# Assignment4B-IR-Sensor_Schematic_sch.net
KiCad netlist of a schematic drawn in EAGLE
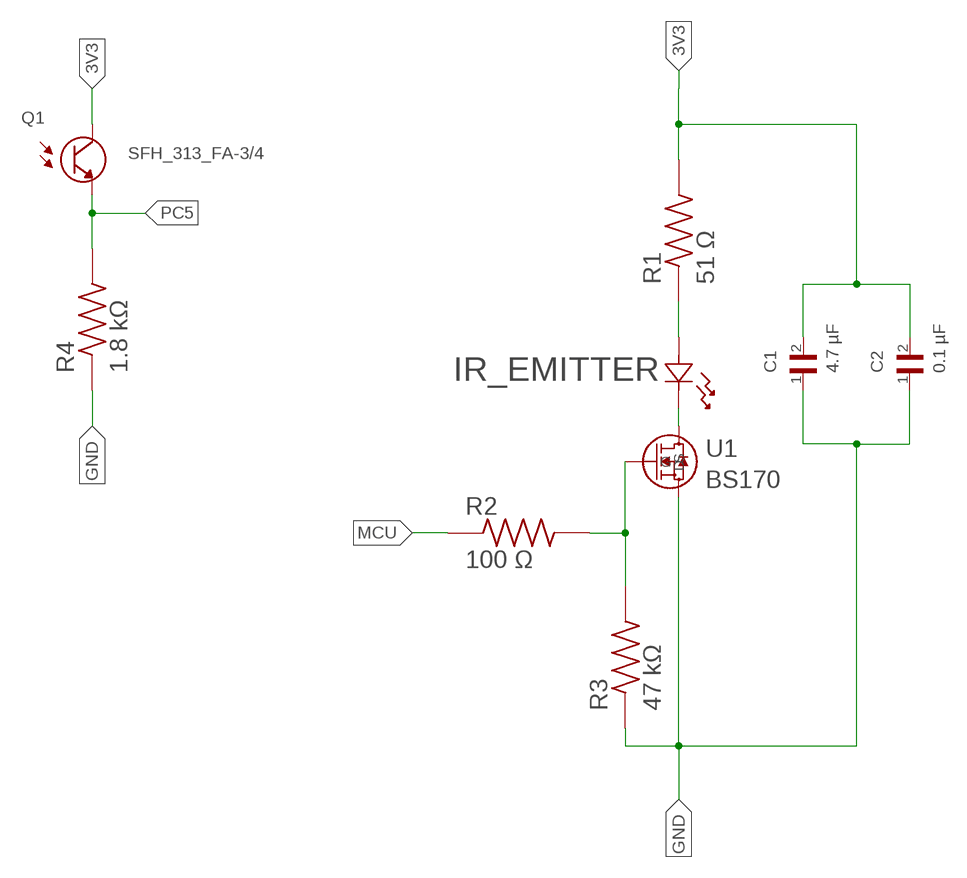
[diagram p0: schematic, sheet 1]

(export (version "E")
  (design (tool "Eeschema 10.0.6"))
  (components
    (comp (ref "C1")
      (value "4.7 µF")
      (footprint "eagle-import:CAPC2012X140N")
      (fields
        (field (name "DIGIKEY_PART_NUMBER") "490-14466-2-ND")
        (field (name "MF") "Murata Electronics")
        (field (name "MP") "GRM21BR71C475KE51L")
      )
      (libsource (lib "eagle-import") (part "GRM21BR71C475KE51L"))
    )
    (comp (ref "C2")
      (value "0.1 µF")
      (footprint "eagle-import:CAPC2012X140N")
      (fields (field (name "MF") "Murata") (field (name "MP") "GCM21BR72A104KA37K"))
      (libsource (lib "eagle-import") (part "GCM21BR72A104KA37K"))
    )
    (comp (ref "LED1")
      (value "IR_EMITTER")
      (footprint "eagle-import:LED_INL-5AMIR15_INO")
      (fields
        (field (name "MANUFACTURER_PART_NUMBER") "INL-5AMIR15")
        (field (name "COPYRIGHT") "Copyright (C) 2024 Ultra Librarian. All rights reserved.")
      )
      (libsource (lib "eagle-import") (part "INL-5AMIR15"))
    )
    (comp (ref "Q1")
      (value "SFH_313_FA-3/4")
      (footprint "eagle-import:XDCR_SFH_313_FA-3_4")
      (fields
        (field (name "DIGIKEY_PART_NUMBER") "475-SFH313FA-3/4-ND")
        (field (name "MF") "OSRAM Opto")
        (field (name "MP") "SFH 313 FA-3/4")
      )
      (libsource (lib "eagle-import") (part "SFH_313_FA-3/4"))
    )
    (comp (ref "R1")
      (value "51 Ω")
      (footprint "eagle-import:RESC2012X60N")
      (fields
        (field (name "DIGIKEY_PART_NUMBER") "541-51.0TTR-ND")
        (field (name "MF") "Vishay")
        (field (name "MP") "CRCW080551R0FKEAHP")
      )
      (libsource (lib "eagle-import") (part "CRCW080551R0FKEAHP"))
    )
    (comp (ref "R2")
      (value "100 Ω")
      (footprint "eagle-import:RESC2012X60N")
      (fields
        (field (name "DIGIKEY_PART_NUMBER") "541-100TTR-ND")
        (field (name "MF") "Vishay")
        (field (name "MP") "CRCW0805100RFKEAHP")
      )
      (libsource (lib "eagle-import") (part "CRCW0805100RFKEAHP"))
    )
    (comp (ref "R3")
      (value "47 kΩ")
      (footprint "eagle-import:RESC2012X50N")
      (fields
        (field (name "DIGIKEY_PART_NUMBER") "541-47KATR-ND")
        (field (name "MF") "Vishay Dale")
        (field (name "MP") "CRCW080547K0JNEA")
      )
      (libsource (lib "eagle-import") (part "CRCW080547K0JNEA"))
    )
    (comp (ref "R4")
      (value "1.8 kΩ")
      (footprint "eagle-import:RESC2012X50N")
      (fields
        (field (name "DIGIKEY_PART_NUMBER") "541-CRCW08051K80FKEBTR-ND")
        (field (name "MF") "Vishay Dale")
        (field (name "MP") "CRCW08051K80FKEB")
      )
      (libsource (lib "eagle-import") (part "CRCW08051K80FKEB"))
    )
    (comp (ref "U1")
      (value "BS170")
      (footprint "eagle-import:TO_SA06_ONS")
      (fields (field (name "COPYRIGHT") "Copyright (C) 2024 Ultra Librarian. All rights reserved."))
      (libsource (lib "eagle-import") (part "BS170"))
    )
  )
  (nets
    (net (code "1") (name "3V3") (class "Default")
      (node (ref "C1") (pin "2") (pinfunction "2_2") (pintype "passive"))
      (node (ref "C2") (pin "2") (pinfunction "2_2") (pintype "passive"))
      (node (ref "Q1") (pin "2") (pinfunction "C_2") (pintype "passive"))
      (node (ref "R1") (pin "2") (pinfunction "2_2") (pintype "passive"))
    )
    (net (code "2") (name "GND") (class "Default")
      (node (ref "C1") (pin "1") (pinfunction "1_1") (pintype "passive"))
      (node (ref "C2") (pin "1") (pinfunction "1_1") (pintype "passive"))
      (node (ref "R3") (pin "1") (pinfunction "1_1") (pintype "passive"))
      (node (ref "R4") (pin "1") (pinfunction "1_1") (pintype "passive"))
      (node (ref "U1") (pin "3") (pinfunction "S_3") (pintype "passive"))
    )
    (net (code "3") (name "MCU") (class "Default")
      (node (ref "R2") (pin "1") (pinfunction "1_1") (pintype "passive"))
    )
    (net (code "4") (name "Net-(LED1-Pad2)") (class "Default")
      (node (ref "LED1") (pin "2") (pinfunction "2_2") (pintype "passive"))
      (node (ref "R1") (pin "1") (pinfunction "1_1") (pintype "passive"))
    )
    (net (code "5") (name "Net-(U1-D)") (class "Default")
      (node (ref "LED1") (pin "1") (pinfunction "1_1") (pintype "passive"))
      (node (ref "U1") (pin "2") (pinfunction "D_2") (pintype "passive"))
    )
    (net (code "6") (name "Net-(U1-G)") (class "Default")
      (node (ref "R2") (pin "2") (pinfunction "2_2") (pintype "passive"))
      (node (ref "R3") (pin "2") (pinfunction "2_2") (pintype "passive"))
      (node (ref "U1") (pin "1") (pinfunction "G_1") (pintype "passive"))
    )
    (net (code "7") (name "PC5") (class "Default")
      (node (ref "Q1") (pin "1") (pinfunction "E_1") (pintype "passive"))
      (node (ref "R4") (pin "2") (pinfunction "2_2") (pintype "passive"))
    )
  )
)
